# 06-JTAG.net
KiCad netlist of a schematic drawn in Altium Designer
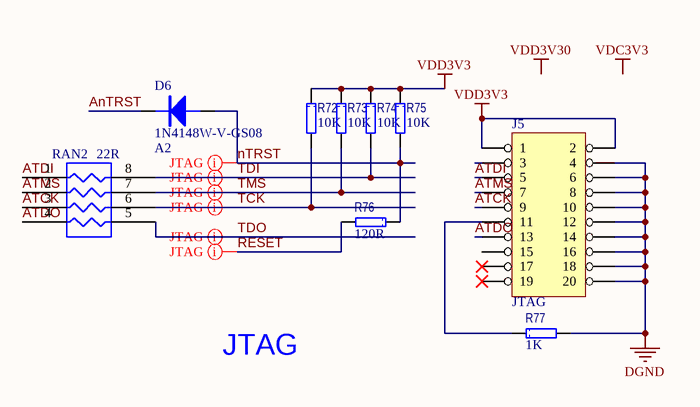
[diagram p0: 06-JTAG.SchDoc]

(export (version "E")
  (design (tool "Eeschema 10.0.6"))
  (components
    (comp (ref "D6")
      (value "1N4148W-V-GS08")
      (footprint "SOD123")
      (description "二极管 - 通用，功率，开关 100V Io/150mA")
      (fields (field (name "MANUFACTURER") "Vishay Semiconductors") (field (name "ALTIUM_VALUE") "A2"))
      (libsource (lib "IN4148") (part "1N4148W"))
    )
    (comp (ref "J5")
      (value "JTAG")
      (footprint "IDC20S")
      (description "插针 CON")
      (libsource (lib "*") (part "HEADER 10X2"))
    )
    (comp (ref "R72")
      (value "10K")
      (footprint "1608[0603]R")
      (description "厚膜电阻器 - SMD 1/10watt 10Kohms 1%")
      (fields
        (field (name "MANUFACTURER") "Vishay / Dale")
        (field (name "MANUFACTURER PART NUMBER") "CRCW060310K0FKEA")
      )
      (libsource (lib "10K 1%") (part "RES"))
    )
    (comp (ref "R73")
      (value "10K")
      (footprint "1608[0603]R")
      (description "厚膜电阻器 - SMD 1/10watt 10Kohms 1%")
      (fields
        (field (name "MANUFACTURER") "Vishay / Dale")
        (field (name "MANUFACTURER PART NUMBER") "CRCW060310K0FKEA")
      )
      (libsource (lib "10K 1%") (part "RES"))
    )
    (comp (ref "R74")
      (value "10K")
      (footprint "1608[0603]R")
      (description "厚膜电阻器 - SMD 1/10watt 10Kohms 1%")
      (fields
        (field (name "MANUFACTURER") "Vishay / Dale")
        (field (name "MANUFACTURER PART NUMBER") "CRCW060310K0FKEA")
      )
      (libsource (lib "10K 1%") (part "RES"))
    )
    (comp (ref "R75")
      (value "10K")
      (footprint "1608[0603]R")
      (description "厚膜电阻器 - SMD 1/10watt 10Kohms 1%")
      (fields
        (field (name "MANUFACTURER") "Vishay / Dale")
        (field (name "MANUFACTURER PART NUMBER") "CRCW060310K0FKEA")
      )
      (libsource (lib "10K 1%") (part "RES"))
    )
    (comp (ref "R76")
      (value "120R")
      (footprint "1608[0603]R")
      (description "厚膜电阻器 - SMD 1/10watt 120ohms 1%")
      (fields
        (field (name "MANUFACTURER") "Vishay / Dale")
        (field (name "MANUFACTURER PART NUMBER") "CRCW0603120RFKEA")
      )
      (libsource (lib "120R 1%") (part "RES"))
    )
    (comp (ref "R77")
      (value "1K")
      (footprint "1608[0603]R")
      (description "厚膜电阻器 - SMD 1/10watt 1.0Kohms 1%")
      (fields
        (field (name "MANUFACTURER") "Vishay / Dale")
        (field (name "MANUFACTURER PART NUMBER") "CRCW06031K00FKEA")
      )
      (libsource (lib "1K 1%") (part "RES"))
    )
    (comp (ref "RAN2")
      (value "22R")
      (footprint "R-AR4")
      (description "电阻器网络与阵列 8Term 22ohms 5% Convex")
      (fields
        (field (name "MANUFACTURER") "Vishay / Dale")
        (field (name "MANUFACTURER PART NUMBER") "CRA06S08322R0JTA")
      )
      (libsource (lib "*") (part "RP4R"))
    )
  )
  (nets
    (net (code "1") (name "/ATCK") (class "Default")
      (node (ref "J5") (pin "9") (pinfunction "9_9") (pintype "passive"))
      (node (ref "RAN2") (pin "3") (pinfunction "R3_3") (pintype "passive"))
    )
    (net (code "2") (name "/ATDI") (class "Default")
      (node (ref "J5") (pin "5") (pinfunction "5_5") (pintype "passive"))
      (node (ref "RAN2") (pin "1") (pinfunction "R1_1") (pintype "passive"))
    )
    (net (code "3") (name "/ATDO") (class "Default")
      (node (ref "J5") (pin "13") (pinfunction "13_13") (pintype "passive"))
      (node (ref "RAN2") (pin "4") (pinfunction "R4_4") (pintype "passive"))
    )
    (net (code "4") (name "/ATMS") (class "Default")
      (node (ref "J5") (pin "7") (pinfunction "7_7") (pintype "passive"))
      (node (ref "RAN2") (pin "2") (pinfunction "R2_2") (pintype "passive"))
    )
    (net (code "5") (name "/AnTRST") (class "Default")
      (node (ref "D6") (pin "2") (pinfunction "K_2") (pintype "passive"))
    )
    (net (code "6") (name "/RESET") (class "Default")
      (node (ref "R76") (pin "2") (pinfunction "2_2") (pintype "passive"))
    )
    (net (code "7") (name "/TCK") (class "Default")
      (node (ref "R72") (pin "2") (pinfunction "2_2") (pintype "passive"))
      (node (ref "RAN2") (pin "6") (pinfunction "R3_6") (pintype "passive"))
    )
    (net (code "8") (name "/TDI") (class "Default")
      (node (ref "R74") (pin "2") (pinfunction "2_2") (pintype "passive"))
      (node (ref "RAN2") (pin "8") (pinfunction "R1_8") (pintype "passive"))
    )
    (net (code "9") (name "/TDO") (class "Default")
      (node (ref "RAN2") (pin "5") (pinfunction "R4_5") (pintype "passive"))
    )
    (net (code "10") (name "/TMS") (class "Default")
      (node (ref "R73") (pin "2") (pinfunction "2_2") (pintype "passive"))
      (node (ref "RAN2") (pin "7") (pinfunction "R2_7") (pintype "passive"))
    )
    (net (code "11") (name "/nTRST") (class "Default")
      (node (ref "D6") (pin "1") (pinfunction "A_1") (pintype "passive"))
      (node (ref "R75") (pin "2") (pinfunction "2_2") (pintype "passive"))
      (node (ref "R76") (pin "1") (pinfunction "1_1") (pintype "passive"))
    )
    (net (code "12") (name "DGND") (class "Default")
      (node (ref "J5") (pin "10") (pinfunction "10_10") (pintype "passive"))
      (node (ref "J5") (pin "12") (pinfunction "12_12") (pintype "passive"))
      (node (ref "J5") (pin "14") (pinfunction "14_14") (pintype "passive"))
      (node (ref "J5") (pin "16") (pinfunction "16_16") (pintype "passive"))
      (node (ref "J5") (pin "18") (pinfunction "18_18") (pintype "passive"))
      (node (ref "J5") (pin "20") (pinfunction "20_20") (pintype "passive"))
      (node (ref "J5") (pin "4") (pinfunction "4_4") (pintype "passive"))
      (node (ref "J5") (pin "6") (pinfunction "6_6") (pintype "passive"))
      (node (ref "J5") (pin "8") (pinfunction "8_8") (pintype "passive"))
      (node (ref "R77") (pin "2") (pinfunction "2_2") (pintype "passive"))
    )
    (net (code "13") (name "Net-(J5-Pad11)") (class "Default")
      (node (ref "J5") (pin "11") (pinfunction "11_11") (pintype "passive"))
      (node (ref "R77") (pin "1") (pinfunction "1_1") (pintype "passive"))
    )
    (net (code "15") (name "VDD3V3") (class "Default")
      (node (ref "J5") (pin "1") (pinfunction "1_1") (pintype "passive"))
      (node (ref "J5") (pin "2") (pinfunction "2_2") (pintype "passive"))
      (node (ref "R72") (pin "1") (pinfunction "1_1") (pintype "passive"))
      (node (ref "R73") (pin "1") (pinfunction "1_1") (pintype "passive"))
      (node (ref "R74") (pin "1") (pinfunction "1_1") (pintype "passive"))
      (node (ref "R75") (pin "1") (pinfunction "1_1") (pintype "passive"))
    )
    (net (code "17") (name "unconnected-(J5-Pad3)") (class "Default")
      (node (ref "J5") (pin "3") (pinfunction "3_3") (pintype "passive"))
    )
    (net (code "18") (name "unconnected-(J5-Pad15)") (class "Default")
      (node (ref "J5") (pin "15") (pinfunction "15_15") (pintype "passive"))
    )
    (net (code "19") (name "unconnected-(J5-Pad17)") (class "Default")
      (node (ref "J5") (pin "17") (pinfunction "17_17") (pintype "passive+no_connect"))
    )
    (net (code "20") (name "unconnected-(J5-Pad19)") (class "Default")
      (node (ref "J5") (pin "19") (pinfunction "19_19") (pintype "passive+no_connect"))
    )
  )
)
